# arduino-day-arduino.net
KiCad netlist of a schematic drawn in EAGLE
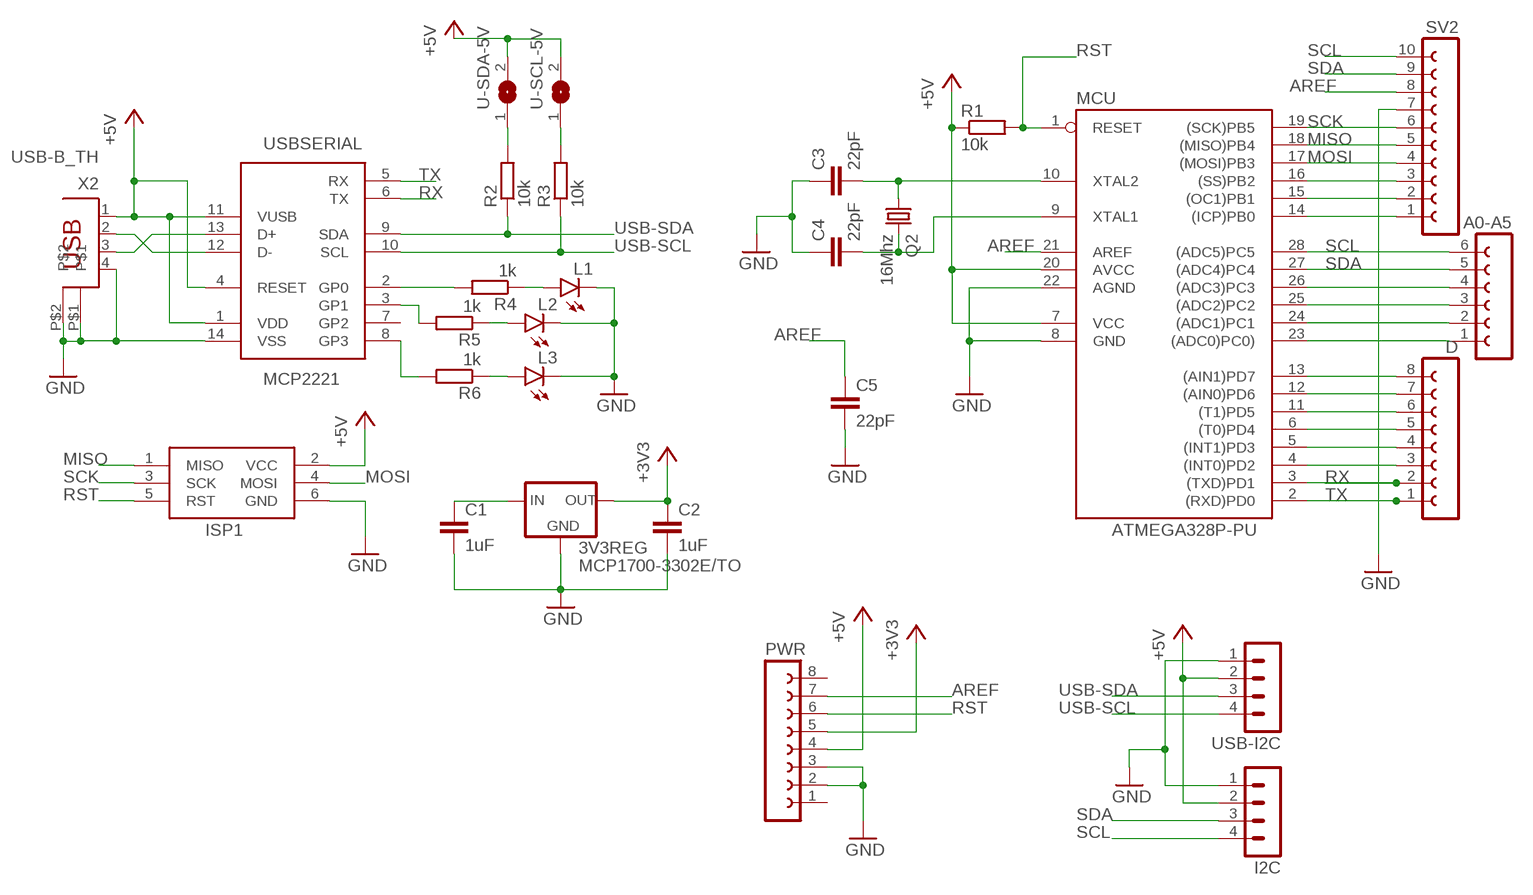
[diagram p0: schematic, sheet 1]

(export (version "E")
  (design (tool "Eeschema 10.0.6"))
  (components
    (comp (ref "3V3REG")
      (value "MCP1700-3302E/TO")
      (footprint "eagle-import:TO92")
      (libsource (lib "eagle-import") (part "MCP1700TRI"))
    )
    (comp (ref "A0-A5")
      (value "FE06-1")
      (footprint "eagle-import:FE06")
      (libsource (lib "eagle-import") (part "FE06-1"))
    )
    (comp (ref "C1")
      (value "1uF")
      (footprint "eagle-import:C025-025X050")
      (libsource (lib "eagle-import") (part "C-EU025-025X050"))
    )
    (comp (ref "C2")
      (value "1uF")
      (footprint "eagle-import:C025-025X050")
      (libsource (lib "eagle-import") (part "C-EU025-025X050"))
    )
    (comp (ref "C3")
      (value "22pF")
      (footprint "eagle-import:C025-025X050")
      (libsource (lib "eagle-import") (part "C-EU025-025X050"))
    )
    (comp (ref "C4")
      (value "22pF")
      (footprint "eagle-import:C025-025X050")
      (libsource (lib "eagle-import") (part "C-EU025-025X050"))
    )
    (comp (ref "C5")
      (value "22pF")
      (footprint "eagle-import:C025-025X050")
      (libsource (lib "eagle-import") (part "C-EU025-025X050"))
    )
    (comp (ref "D")
      (value "FE08-1")
      (footprint "eagle-import:FE08")
      (libsource (lib "eagle-import") (part "FE08-1"))
    )
    (comp (ref "I2C")
      (value "MA04-1")
      (footprint "eagle-import:MA04-1")
      (libsource (lib "eagle-import") (part "MA04-1"))
    )
    (comp (ref "ISP1")
      (value "AVRISP-6")
      (footprint "eagle-import:AVRISP")
      (libsource (lib "eagle-import") (part "AVRISP-6"))
    )
    (comp (ref "L1")
      (value "LED3MM")
      (footprint "eagle-import:LED3MM")
      (libsource (lib "eagle-import") (part "LED3MM"))
    )
    (comp (ref "L2")
      (value "LED3MM")
      (footprint "eagle-import:LED3MM")
      (libsource (lib "eagle-import") (part "LED3MM"))
    )
    (comp (ref "L3")
      (value "LED3MM")
      (footprint "eagle-import:LED3MM")
      (libsource (lib "eagle-import") (part "LED3MM"))
    )
    (comp (ref "MCU")
      (value "ATMEGA328P-PU")
      (footprint "eagle-import:DIL28-3")
      (libsource (lib "eagle-import") (part "ATMEGA328P-PU"))
    )
    (comp (ref "PWR")
      (value "FE08-1")
      (footprint "eagle-import:FE08")
      (libsource (lib "eagle-import") (part "FE08-1"))
    )
    (comp (ref "Q2")
      (value "16Mhz")
      (footprint "eagle-import:HC49_S")
      (libsource (lib "eagle-import") (part "CRYSTALHC49S"))
    )
    (comp (ref "R1")
      (value "10k")
      (footprint "eagle-import:0204_7")
      (libsource (lib "eagle-import") (part "R-EU_0204/7"))
    )
    (comp (ref "R2")
      (value "10k")
      (footprint "eagle-import:0204_7")
      (libsource (lib "eagle-import") (part "R-EU_0204/7"))
    )
    (comp (ref "R3")
      (value "10k")
      (footprint "eagle-import:0204_7")
      (libsource (lib "eagle-import") (part "R-EU_0204/7"))
    )
    (comp (ref "R4")
      (value "1k")
      (footprint "eagle-import:0204_7")
      (libsource (lib "eagle-import") (part "R-EU_0204/7"))
    )
    (comp (ref "R5")
      (value "1k")
      (footprint "eagle-import:0204_7")
      (libsource (lib "eagle-import") (part "R-EU_0204/7"))
    )
    (comp (ref "R6")
      (value "1k")
      (footprint "eagle-import:0204_7")
      (libsource (lib "eagle-import") (part "R-EU_0204/7"))
    )
    (comp (ref "SV2")
      (value "FE10-1")
      (footprint "eagle-import:FE10")
      (libsource (lib "eagle-import") (part "FE10-1"))
    )
    (comp (ref "U-SCL-5V")
      (value "SJW")
      (footprint "eagle-import:SJW")
      (libsource (lib "eagle-import") (part "SJW"))
    )
    (comp (ref "U-SDA-5V")
      (value "SJW")
      (footprint "eagle-import:SJW")
      (libsource (lib "eagle-import") (part "SJW"))
    )
    (comp (ref "USB-I2C")
      (value "MA04-1")
      (footprint "eagle-import:MA04-1")
      (libsource (lib "eagle-import") (part "MA04-1"))
    )
    (comp (ref "USBSERIAL")
      (value "MCP2221")
      (footprint "eagle-import:DIL14")
      (libsource (lib "eagle-import") (part "MCP2221"))
    )
    (comp (ref "X2")
      (value "USB-B_TH")
      (footprint "eagle-import:PN61729")
      (libsource (lib "eagle-import") (part "PN61729"))
    )
  )
  (nets
    (net (code "1") (name "+3V3") (class "Default")
      (node (ref "3V3REG") (pin "3") (pinfunction "OUT_3") (pintype "passive"))
      (node (ref "C2") (pin "1") (pinfunction "1_1") (pintype "passive"))
      (node (ref "PWR") (pin "5") (pinfunction "5_5") (pintype "passive"))
    )
    (net (code "2") (name "+5V") (class "Default")
      (node (ref "I2C") (pin "2") (pinfunction "2_2") (pintype "passive"))
      (node (ref "ISP1") (pin "2") (pinfunction "VCC_2") (pintype "power_in"))
      (node (ref "MCU") (pin "20") (pinfunction "AVCC_20") (pintype "power_in"))
      (node (ref "MCU") (pin "7") (pinfunction "VCC_7") (pintype "power_in"))
      (node (ref "PWR") (pin "4") (pinfunction "4_4") (pintype "passive"))
      (node (ref "R1") (pin "1") (pinfunction "1_1") (pintype "passive"))
      (node (ref "U-SCL-5V") (pin "2") (pinfunction "2_2") (pintype "passive"))
      (node (ref "U-SDA-5V") (pin "2") (pinfunction "2_2") (pintype "passive"))
      (node (ref "USB-I2C") (pin "2") (pinfunction "2_2") (pintype "passive"))
      (node (ref "USBSERIAL") (pin "1") (pinfunction "VDD_1") (pintype "bidirectional"))
      (node (ref "USBSERIAL") (pin "11") (pinfunction "VUSB_11") (pintype "bidirectional"))
      (node (ref "USBSERIAL") (pin "4") (pinfunction "RESET_4") (pintype "bidirectional"))
      (node (ref "X2") (pin "1") (pinfunction "1_1") (pintype "bidirectional"))
    )
    (net (code "3") (name "/AREF") (class "Default")
      (node (ref "C5") (pin "1") (pinfunction "1_1") (pintype "passive"))
      (node (ref "MCU") (pin "21") (pinfunction "AREF_21") (pintype "passive"))
      (node (ref "PWR") (pin "7") (pinfunction "7_7") (pintype "passive"))
      (node (ref "SV2") (pin "8") (pinfunction "8_8") (pintype "passive"))
    )
    (net (code "4") (name "/MISO") (class "Default")
      (node (ref "ISP1") (pin "1") (pinfunction "MISO_1") (pintype "input"))
      (node (ref "MCU") (pin "18") (pinfunction "(MISO)PB4_18") (pintype "bidirectional"))
      (node (ref "SV2") (pin "5") (pinfunction "5_5") (pintype "passive"))
    )
    (net (code "5") (name "/MOSI") (class "Default")
      (node (ref "ISP1") (pin "4") (pinfunction "MOSI_4") (pintype "output"))
      (node (ref "MCU") (pin "17") (pinfunction "(MOSI)PB3_17") (pintype "bidirectional"))
      (node (ref "SV2") (pin "4") (pinfunction "4_4") (pintype "passive"))
    )
    (net (code "6") (name "/RST") (class "Default")
      (node (ref "ISP1") (pin "5") (pinfunction "RST_5") (pintype "output"))
      (node (ref "MCU") (pin "1") (pinfunction "RESET_1") (pintype "input"))
      (node (ref "PWR") (pin "6") (pinfunction "6_6") (pintype "passive"))
      (node (ref "R1") (pin "2") (pinfunction "2_2") (pintype "passive"))
    )
    (net (code "7") (name "/RX") (class "Default")
      (node (ref "D") (pin "2") (pinfunction "2_2") (pintype "passive"))
      (node (ref "MCU") (pin "3") (pinfunction "(TXD)PD1_3") (pintype "bidirectional"))
      (node (ref "USBSERIAL") (pin "6") (pinfunction "TX_6") (pintype "bidirectional"))
    )
    (net (code "8") (name "/SCK") (class "Default")
      (node (ref "ISP1") (pin "3") (pinfunction "SCK_3") (pintype "output"))
      (node (ref "MCU") (pin "19") (pinfunction "(SCK)PB5_19") (pintype "bidirectional"))
      (node (ref "SV2") (pin "6") (pinfunction "6_6") (pintype "passive"))
    )
    (net (code "9") (name "/SCL") (class "Default")
      (node (ref "A0-A5") (pin "6") (pinfunction "6_6") (pintype "passive"))
      (node (ref "I2C") (pin "4") (pinfunction "4_4") (pintype "passive"))
      (node (ref "MCU") (pin "28") (pinfunction "(ADC5)PC5_28") (pintype "bidirectional"))
      (node (ref "SV2") (pin "10") (pinfunction "10_10") (pintype "passive"))
    )
    (net (code "10") (name "/SDA") (class "Default")
      (node (ref "A0-A5") (pin "5") (pinfunction "5_5") (pintype "passive"))
      (node (ref "I2C") (pin "3") (pinfunction "3_3") (pintype "passive"))
      (node (ref "MCU") (pin "27") (pinfunction "(ADC4)PC4_27") (pintype "bidirectional"))
      (node (ref "SV2") (pin "9") (pinfunction "9_9") (pintype "passive"))
    )
    (net (code "11") (name "/TX") (class "Default")
      (node (ref "D") (pin "1") (pinfunction "1_1") (pintype "passive"))
      (node (ref "MCU") (pin "2") (pinfunction "(RXD)PD0_2") (pintype "bidirectional"))
      (node (ref "USBSERIAL") (pin "5") (pinfunction "RX_5") (pintype "bidirectional"))
    )
    (net (code "12") (name "/USB-SCL") (class "Default")
      (node (ref "R3") (pin "1") (pinfunction "1_1") (pintype "passive"))
      (node (ref "USB-I2C") (pin "4") (pinfunction "4_4") (pintype "passive"))
      (node (ref "USBSERIAL") (pin "10") (pinfunction "SCL_10") (pintype "bidirectional"))
    )
    (net (code "13") (name "/USB-SDA") (class "Default")
      (node (ref "R2") (pin "1") (pinfunction "1_1") (pintype "passive"))
      (node (ref "USB-I2C") (pin "3") (pinfunction "3_3") (pintype "passive"))
      (node (ref "USBSERIAL") (pin "9") (pinfunction "SDA_9") (pintype "bidirectional"))
    )
    (net (code "14") (name "GND") (class "Default")
      (node (ref "3V3REG") (pin "1") (pinfunction "GND_1") (pintype "input"))
      (node (ref "C1") (pin "2") (pinfunction "2_2") (pintype "passive"))
      (node (ref "C2") (pin "2") (pinfunction "2_2") (pintype "passive"))
      (node (ref "C3") (pin "1") (pinfunction "1_1") (pintype "passive"))
      (node (ref "C4") (pin "1") (pinfunction "1_1") (pintype "passive"))
      (node (ref "C5") (pin "2") (pinfunction "2_2") (pintype "passive"))
      (node (ref "I2C") (pin "1") (pinfunction "1_1") (pintype "passive"))
      (node (ref "ISP1") (pin "6") (pinfunction "GND_6") (pintype "power_in"))
      (node (ref "L1") (pin "K") (pinfunction "C_K") (pintype "passive"))
      (node (ref "L2") (pin "K") (pinfunction "C_K") (pintype "passive"))
      (node (ref "L3") (pin "K") (pinfunction "C_K") (pintype "passive"))
      (node (ref "MCU") (pin "22") (pinfunction "AGND_22") (pintype "power_in"))
      (node (ref "MCU") (pin "8") (pinfunction "GND_8") (pintype "power_in"))
      (node (ref "PWR") (pin "2") (pinfunction "2_2") (pintype "passive"))
      (node (ref "PWR") (pin "3") (pinfunction "3_3") (pintype "passive"))
      (node (ref "SV2") (pin "7") (pinfunction "7_7") (pintype "passive"))
      (node (ref "USB-I2C") (pin "1") (pinfunction "1_1") (pintype "passive"))
      (node (ref "USBSERIAL") (pin "14") (pinfunction "VSS_14") (pintype "bidirectional"))
      (node (ref "X2") (pin "4") (pinfunction "4_4") (pintype "bidirectional"))
      (node (ref "X2") (pin "P$1") (pinfunction "P$1_P$1") (pintype "bidirectional"))
      (node (ref "X2") (pin "P$2") (pinfunction "P$2_P$2") (pintype "bidirectional"))
    )
    (net (code "15") (name "Net-(3V3REG-IN)") (class "Default")
      (node (ref "3V3REG") (pin "2") (pinfunction "IN_2") (pintype "input"))
      (node (ref "C1") (pin "1") (pinfunction "1_1") (pintype "passive"))
    )
    (net (code "16") (name "Net-(L1-PadA)") (class "Default")
      (node (ref "L1") (pin "A") (pinfunction "A_A") (pintype "passive"))
      (node (ref "R4") (pin "1") (pinfunction "1_1") (pintype "passive"))
    )
    (net (code "17") (name "Net-(L2-PadA)") (class "Default")
      (node (ref "L2") (pin "A") (pinfunction "A_A") (pintype "passive"))
      (node (ref "R5") (pin "1") (pinfunction "1_1") (pintype "passive"))
    )
    (net (code "18") (name "Net-(L3-PadA)") (class "Default")
      (node (ref "L3") (pin "A") (pinfunction "A_A") (pintype "passive"))
      (node (ref "R6") (pin "1") (pinfunction "1_1") (pintype "passive"))
    )
    (net (code "19") (name "Net-(MCU-(ADC0)PC0))") (class "Default")
      (node (ref "A0-A5") (pin "1") (pinfunction "1_1") (pintype "passive"))
      (node (ref "MCU") (pin "23") (pinfunction "(ADC0)PC0)_23") (pintype "bidirectional"))
    )
    (net (code "20") (name "Net-(MCU-(ADC1)PC1)") (class "Default")
      (node (ref "A0-A5") (pin "2") (pinfunction "2_2") (pintype "passive"))
      (node (ref "MCU") (pin "24") (pinfunction "(ADC1)PC1_24") (pintype "bidirectional"))
    )
    (net (code "21") (name "Net-(MCU-(ADC2)PC2)") (class "Default")
      (node (ref "A0-A5") (pin "3") (pinfunction "3_3") (pintype "passive"))
      (node (ref "MCU") (pin "25") (pinfunction "(ADC2)PC2_25") (pintype "bidirectional"))
    )
    (net (code "22") (name "Net-(MCU-(ADC3)PC3)") (class "Default")
      (node (ref "A0-A5") (pin "4") (pinfunction "4_4") (pintype "passive"))
      (node (ref "MCU") (pin "26") (pinfunction "(ADC3)PC3_26") (pintype "bidirectional"))
    )
    (net (code "23") (name "Net-(MCU-(AIN0)PD6)") (class "Default")
      (node (ref "D") (pin "7") (pinfunction "7_7") (pintype "passive"))
      (node (ref "MCU") (pin "12") (pinfunction "(AIN0)PD6_12") (pintype "bidirectional"))
    )
    (net (code "24") (name "Net-(MCU-(AIN1)PD7)") (class "Default")
      (node (ref "D") (pin "8") (pinfunction "8_8") (pintype "passive"))
      (node (ref "MCU") (pin "13") (pinfunction "(AIN1)PD7_13") (pintype "bidirectional"))
    )
    (net (code "25") (name "Net-(MCU-(ICP)PB0)") (class "Default")
      (node (ref "MCU") (pin "14") (pinfunction "(ICP)PB0_14") (pintype "bidirectional"))
      (node (ref "SV2") (pin "1") (pinfunction "1_1") (pintype "passive"))
    )
    (net (code "26") (name "Net-(MCU-(INT0)PD2)") (class "Default")
      (node (ref "D") (pin "3") (pinfunction "3_3") (pintype "passive"))
      (node (ref "MCU") (pin "4") (pinfunction "(INT0)PD2_4") (pintype "bidirectional"))
    )
    (net (code "27") (name "Net-(MCU-(INT1)PD3)") (class "Default")
      (node (ref "D") (pin "4") (pinfunction "4_4") (pintype "passive"))
      (node (ref "MCU") (pin "5") (pinfunction "(INT1)PD3_5") (pintype "bidirectional"))
    )
    (net (code "28") (name "Net-(MCU-(OC1)PB1)") (class "Default")
      (node (ref "MCU") (pin "15") (pinfunction "(OC1)PB1_15") (pintype "bidirectional"))
      (node (ref "SV2") (pin "2") (pinfunction "2_2") (pintype "passive"))
    )
    (net (code "29") (name "Net-(MCU-(SS)PB2)") (class "Default")
      (node (ref "MCU") (pin "16") (pinfunction "(SS)PB2_16") (pintype "bidirectional"))
      (node (ref "SV2") (pin "3") (pinfunction "3_3") (pintype "passive"))
    )
    (net (code "30") (name "Net-(MCU-(T0)PD4)") (class "Default")
      (node (ref "D") (pin "5") (pinfunction "5_5") (pintype "passive"))
      (node (ref "MCU") (pin "6") (pinfunction "(T0)PD4_6") (pintype "bidirectional"))
    )
    (net (code "31") (name "Net-(MCU-(T1)PD5)") (class "Default")
      (node (ref "D") (pin "6") (pinfunction "6_6") (pintype "passive"))
      (node (ref "MCU") (pin "11") (pinfunction "(T1)PD5_11") (pintype "bidirectional"))
    )
    (net (code "32") (name "Net-(MCU-XTAL1)") (class "Default")
      (node (ref "C4") (pin "2") (pinfunction "2_2") (pintype "passive"))
      (node (ref "MCU") (pin "9") (pinfunction "XTAL1_9") (pintype "bidirectional"))
      (node (ref "Q2") (pin "2") (pinfunction "2_2") (pintype "passive"))
    )
    (net (code "33") (name "Net-(MCU-XTAL2)") (class "Default")
      (node (ref "C3") (pin "2") (pinfunction "2_2") (pintype "passive"))
      (node (ref "MCU") (pin "10") (pinfunction "XTAL2_10") (pintype "bidirectional"))
      (node (ref "Q2") (pin "1") (pinfunction "1_1") (pintype "passive"))
    )
    (net (code "34") (name "Net-(R2-Pad2)") (class "Default")
      (node (ref "R2") (pin "2") (pinfunction "2_2") (pintype "passive"))
      (node (ref "U-SDA-5V") (pin "1") (pinfunction "1_1") (pintype "passive"))
    )
    (net (code "35") (name "Net-(R3-Pad2)") (class "Default")
      (node (ref "R3") (pin "2") (pinfunction "2_2") (pintype "passive"))
      (node (ref "U-SCL-5V") (pin "1") (pinfunction "1_1") (pintype "passive"))
    )
    (net (code "36") (name "Net-(USBSERIAL-D+)") (class "Default")
      (node (ref "USBSERIAL") (pin "13") (pinfunction "D+_13") (pintype "bidirectional"))
      (node (ref "X2") (pin "3") (pinfunction "3_3") (pintype "bidirectional"))
    )
    (net (code "37") (name "Net-(USBSERIAL-D-)") (class "Default")
      (node (ref "USBSERIAL") (pin "12") (pinfunction "D-_12") (pintype "bidirectional"))
      (node (ref "X2") (pin "2") (pinfunction "2_2") (pintype "bidirectional"))
    )
    (net (code "38") (name "Net-(USBSERIAL-GP0)") (class "Default")
      (node (ref "R4") (pin "2") (pinfunction "2_2") (pintype "passive"))
      (node (ref "USBSERIAL") (pin "2") (pinfunction "GP0_2") (pintype "bidirectional"))
    )
    (net (code "39") (name "Net-(USBSERIAL-GP1)") (class "Default")
      (node (ref "R5") (pin "2") (pinfunction "2_2") (pintype "passive"))
      (node (ref "USBSERIAL") (pin "3") (pinfunction "GP1_3") (pintype "bidirectional"))
    )
    (net (code "40") (name "Net-(USBSERIAL-GP3)") (class "Default")
      (node (ref "R6") (pin "2") (pinfunction "2_2") (pintype "passive"))
      (node (ref "USBSERIAL") (pin "8") (pinfunction "GP3_8") (pintype "bidirectional"))
    )
    (net (code "41") (name "unconnected-(PWR-Pad1)") (class "Default")
      (node (ref "PWR") (pin "1") (pinfunction "1_1") (pintype "passive"))
    )
    (net (code "42") (name "unconnected-(PWR-Pad8)") (class "Default")
      (node (ref "PWR") (pin "8") (pinfunction "8_8") (pintype "passive"))
    )
    (net (code "43") (name "unconnected-(USBSERIAL-GP2-Pad7)") (class "Default")
      (node (ref "USBSERIAL") (pin "7") (pinfunction "GP2_7") (pintype "bidirectional"))
    )
  )
)
